# untitled.net
KiCad netlist of a schematic drawn in EAGLE
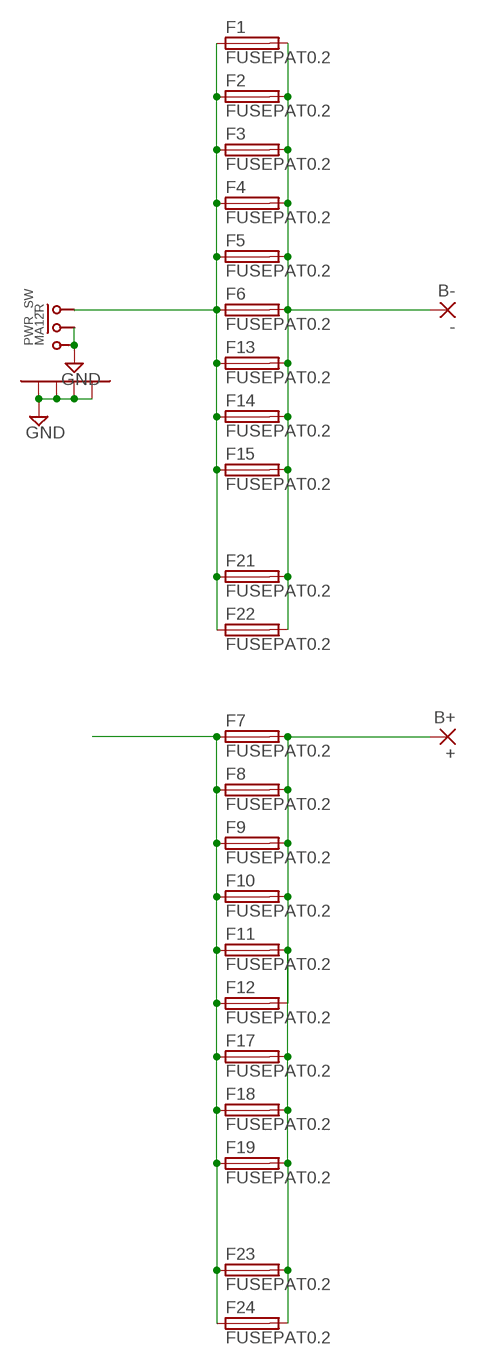
[diagram p0: schematic, sheet 1]

(export (version "E")
  (design (tool "Eeschema 10.0.6"))
  (components
    (comp (ref "B+")
      (value "+")
      (footprint "eagle-import:SMD2,5-5")
      (libsource (lib "eagle-import") (part "PAD2.5-5"))
    )
    (comp (ref "B-")
      (value "-")
      (footprint "eagle-import:SMD2,5-5")
      (libsource (lib "eagle-import") (part "PAD2.5-5"))
    )
    (comp (ref "F1")
      (value "FUSEPAT0.2")
      (footprint "eagle-import:FUSE_PAT1")
      (libsource (lib "eagle-import") (part "FUSEPAT0.2"))
    )
    (comp (ref "F2")
      (value "FUSEPAT0.2")
      (footprint "eagle-import:FUSE_PAT1")
      (libsource (lib "eagle-import") (part "FUSEPAT0.2"))
    )
    (comp (ref "F3")
      (value "FUSEPAT0.2")
      (footprint "eagle-import:FUSE_PAT1")
      (libsource (lib "eagle-import") (part "FUSEPAT0.2"))
    )
    (comp (ref "F4")
      (value "FUSEPAT0.2")
      (footprint "eagle-import:FUSE_PAT1")
      (libsource (lib "eagle-import") (part "FUSEPAT0.2"))
    )
    (comp (ref "F5")
      (value "FUSEPAT0.2")
      (footprint "eagle-import:FUSE_PAT1")
      (libsource (lib "eagle-import") (part "FUSEPAT0.2"))
    )
    (comp (ref "F6")
      (value "FUSEPAT0.2")
      (footprint "eagle-import:FUSE_PAT1")
      (libsource (lib "eagle-import") (part "FUSEPAT0.2"))
    )
    (comp (ref "F7")
      (value "FUSEPAT0.2")
      (footprint "eagle-import:FUSE_PAT1")
      (libsource (lib "eagle-import") (part "FUSEPAT0.2"))
    )
    (comp (ref "F8")
      (value "FUSEPAT0.2")
      (footprint "eagle-import:FUSE_PAT1")
      (libsource (lib "eagle-import") (part "FUSEPAT0.2"))
    )
    (comp (ref "F9")
      (value "FUSEPAT0.2")
      (footprint "eagle-import:FUSE_PAT1")
      (libsource (lib "eagle-import") (part "FUSEPAT0.2"))
    )
    (comp (ref "F10")
      (value "FUSEPAT0.2")
      (footprint "eagle-import:FUSE_PAT1")
      (libsource (lib "eagle-import") (part "FUSEPAT0.2"))
    )
    (comp (ref "F11")
      (value "FUSEPAT0.2")
      (footprint "eagle-import:FUSE_PAT1")
      (libsource (lib "eagle-import") (part "FUSEPAT0.2"))
    )
    (comp (ref "F12")
      (value "FUSEPAT0.2")
      (footprint "eagle-import:FUSE_PAT1")
      (libsource (lib "eagle-import") (part "FUSEPAT0.2"))
    )
    (comp (ref "F13")
      (value "FUSEPAT0.2")
      (footprint "eagle-import:FUSE_PAT1")
      (libsource (lib "eagle-import") (part "FUSEPAT0.2"))
    )
    (comp (ref "F14")
      (value "FUSEPAT0.2")
      (footprint "eagle-import:FUSE_PAT1")
      (libsource (lib "eagle-import") (part "FUSEPAT0.2"))
    )
    (comp (ref "F15")
      (value "FUSEPAT0.2")
      (footprint "eagle-import:FUSE_PAT1")
      (libsource (lib "eagle-import") (part "FUSEPAT0.2"))
    )
    (comp (ref "F17")
      (value "FUSEPAT0.2")
      (footprint "eagle-import:FUSE_PAT1")
      (libsource (lib "eagle-import") (part "FUSEPAT0.2"))
    )
    (comp (ref "F18")
      (value "FUSEPAT0.2")
      (footprint "eagle-import:FUSE_PAT1")
      (libsource (lib "eagle-import") (part "FUSEPAT0.2"))
    )
    (comp (ref "F19")
      (value "FUSEPAT0.2")
      (footprint "eagle-import:FUSE_PAT1")
      (libsource (lib "eagle-import") (part "FUSEPAT0.2"))
    )
    (comp (ref "F21")
      (value "FUSEPAT0.2")
      (footprint "eagle-import:FUSE_PAT1")
      (libsource (lib "eagle-import") (part "FUSEPAT0.2"))
    )
    (comp (ref "F22")
      (value "FUSEPAT0.2")
      (footprint "eagle-import:FUSE_PAT1")
      (libsource (lib "eagle-import") (part "FUSEPAT0.2"))
    )
    (comp (ref "F23")
      (value "FUSEPAT0.2")
      (footprint "eagle-import:FUSE_PAT1")
      (libsource (lib "eagle-import") (part "FUSEPAT0.2"))
    )
    (comp (ref "F24")
      (value "FUSEPAT0.2")
      (footprint "eagle-import:FUSE_PAT1")
      (libsource (lib "eagle-import") (part "FUSEPAT0.2"))
    )
    (comp (ref "PWR_SW")
      (value "MA12R")
      (footprint "eagle-import:MA12R")
      (libsource (lib "eagle-import") (part "MA12R"))
    )
  )
  (nets
    (net (code "1") (name "GND") (class "Default")
      (node (ref "PWR_SW") (pin "P$2") (pinfunction "2_P$2") (pintype "bidirectional"))
      (node (ref "PWR_SW") (pin "P$3") (pinfunction "3_P$3") (pintype "bidirectional"))
      (node (ref "PWR_SW") (pin "P$4") (pinfunction "P$1_P$4") (pintype "bidirectional"))
      (node (ref "PWR_SW") (pin "P$5") (pinfunction "P$2_P$5") (pintype "bidirectional"))
      (node (ref "PWR_SW") (pin "P$6") (pinfunction "P$3_P$6") (pintype "bidirectional"))
      (node (ref "PWR_SW") (pin "P$7") (pinfunction "P$4_P$7") (pintype "bidirectional"))
    )
    (net (code "2") (name "Net-(B+-P)") (class "Default")
      (node (ref "B+") (pin "1") (pinfunction "P_1") (pintype "passive"))
      (node (ref "F10") (pin "P$2") (pinfunction "2_P$2") (pintype "passive"))
      (node (ref "F11") (pin "P$2") (pinfunction "2_P$2") (pintype "passive"))
      (node (ref "F12") (pin "P$2") (pinfunction "2_P$2") (pintype "passive"))
      (node (ref "F17") (pin "P$2") (pinfunction "2_P$2") (pintype "passive"))
      (node (ref "F18") (pin "P$2") (pinfunction "2_P$2") (pintype "passive"))
      (node (ref "F19") (pin "P$2") (pinfunction "2_P$2") (pintype "passive"))
      (node (ref "F23") (pin "P$2") (pinfunction "2_P$2") (pintype "passive"))
      (node (ref "F24") (pin "P$2") (pinfunction "2_P$2") (pintype "passive"))
      (node (ref "F7") (pin "P$2") (pinfunction "2_P$2") (pintype "passive"))
      (node (ref "F8") (pin "P$2") (pinfunction "2_P$2") (pintype "passive"))
      (node (ref "F9") (pin "P$2") (pinfunction "2_P$2") (pintype "passive"))
    )
    (net (code "3") (name "Net-(B--P)") (class "Default")
      (node (ref "B-") (pin "1") (pinfunction "P_1") (pintype "passive"))
      (node (ref "F1") (pin "P$2") (pinfunction "2_P$2") (pintype "passive"))
      (node (ref "F13") (pin "P$2") (pinfunction "2_P$2") (pintype "passive"))
      (node (ref "F14") (pin "P$2") (pinfunction "2_P$2") (pintype "passive"))
      (node (ref "F15") (pin "P$2") (pinfunction "2_P$2") (pintype "passive"))
      (node (ref "F2") (pin "P$2") (pinfunction "2_P$2") (pintype "passive"))
      (node (ref "F21") (pin "P$2") (pinfunction "2_P$2") (pintype "passive"))
      (node (ref "F22") (pin "P$2") (pinfunction "2_P$2") (pintype "passive"))
      (node (ref "F3") (pin "P$2") (pinfunction "2_P$2") (pintype "passive"))
      (node (ref "F4") (pin "P$2") (pinfunction "2_P$2") (pintype "passive"))
      (node (ref "F5") (pin "P$2") (pinfunction "2_P$2") (pintype "passive"))
      (node (ref "F6") (pin "P$2") (pinfunction "2_P$2") (pintype "passive"))
    )
    (net (code "4") (name "Net-(F1-1)") (class "Default")
      (node (ref "F1") (pin "P$1") (pinfunction "1_P$1") (pintype "passive"))
      (node (ref "F13") (pin "P$1") (pinfunction "1_P$1") (pintype "passive"))
      (node (ref "F14") (pin "P$1") (pinfunction "1_P$1") (pintype "passive"))
      (node (ref "F15") (pin "P$1") (pinfunction "1_P$1") (pintype "passive"))
      (node (ref "F2") (pin "P$1") (pinfunction "1_P$1") (pintype "passive"))
      (node (ref "F21") (pin "P$1") (pinfunction "1_P$1") (pintype "passive"))
      (node (ref "F22") (pin "P$1") (pinfunction "1_P$1") (pintype "passive"))
      (node (ref "F3") (pin "P$1") (pinfunction "1_P$1") (pintype "passive"))
      (node (ref "F4") (pin "P$1") (pinfunction "1_P$1") (pintype "passive"))
      (node (ref "F5") (pin "P$1") (pinfunction "1_P$1") (pintype "passive"))
      (node (ref "F6") (pin "P$1") (pinfunction "1_P$1") (pintype "passive"))
      (node (ref "PWR_SW") (pin "P$1") (pinfunction "1_P$1") (pintype "bidirectional"))
    )
    (net (code "5") (name "Net-(F10-1)") (class "Default")
      (node (ref "F10") (pin "P$1") (pinfunction "1_P$1") (pintype "passive"))
      (node (ref "F11") (pin "P$1") (pinfunction "1_P$1") (pintype "passive"))
      (node (ref "F12") (pin "P$1") (pinfunction "1_P$1") (pintype "passive"))
      (node (ref "F17") (pin "P$1") (pinfunction "1_P$1") (pintype "passive"))
      (node (ref "F18") (pin "P$1") (pinfunction "1_P$1") (pintype "passive"))
      (node (ref "F19") (pin "P$1") (pinfunction "1_P$1") (pintype "passive"))
      (node (ref "F23") (pin "P$1") (pinfunction "1_P$1") (pintype "passive"))
      (node (ref "F24") (pin "P$1") (pinfunction "1_P$1") (pintype "passive"))
      (node (ref "F7") (pin "P$1") (pinfunction "1_P$1") (pintype "passive"))
      (node (ref "F8") (pin "P$1") (pinfunction "1_P$1") (pintype "passive"))
      (node (ref "F9") (pin "P$1") (pinfunction "1_P$1") (pintype "passive"))
    )
  )
)
